# PSU_MGTAVTT_Buck.net
KiCad netlist of a schematic drawn in Altium Designer
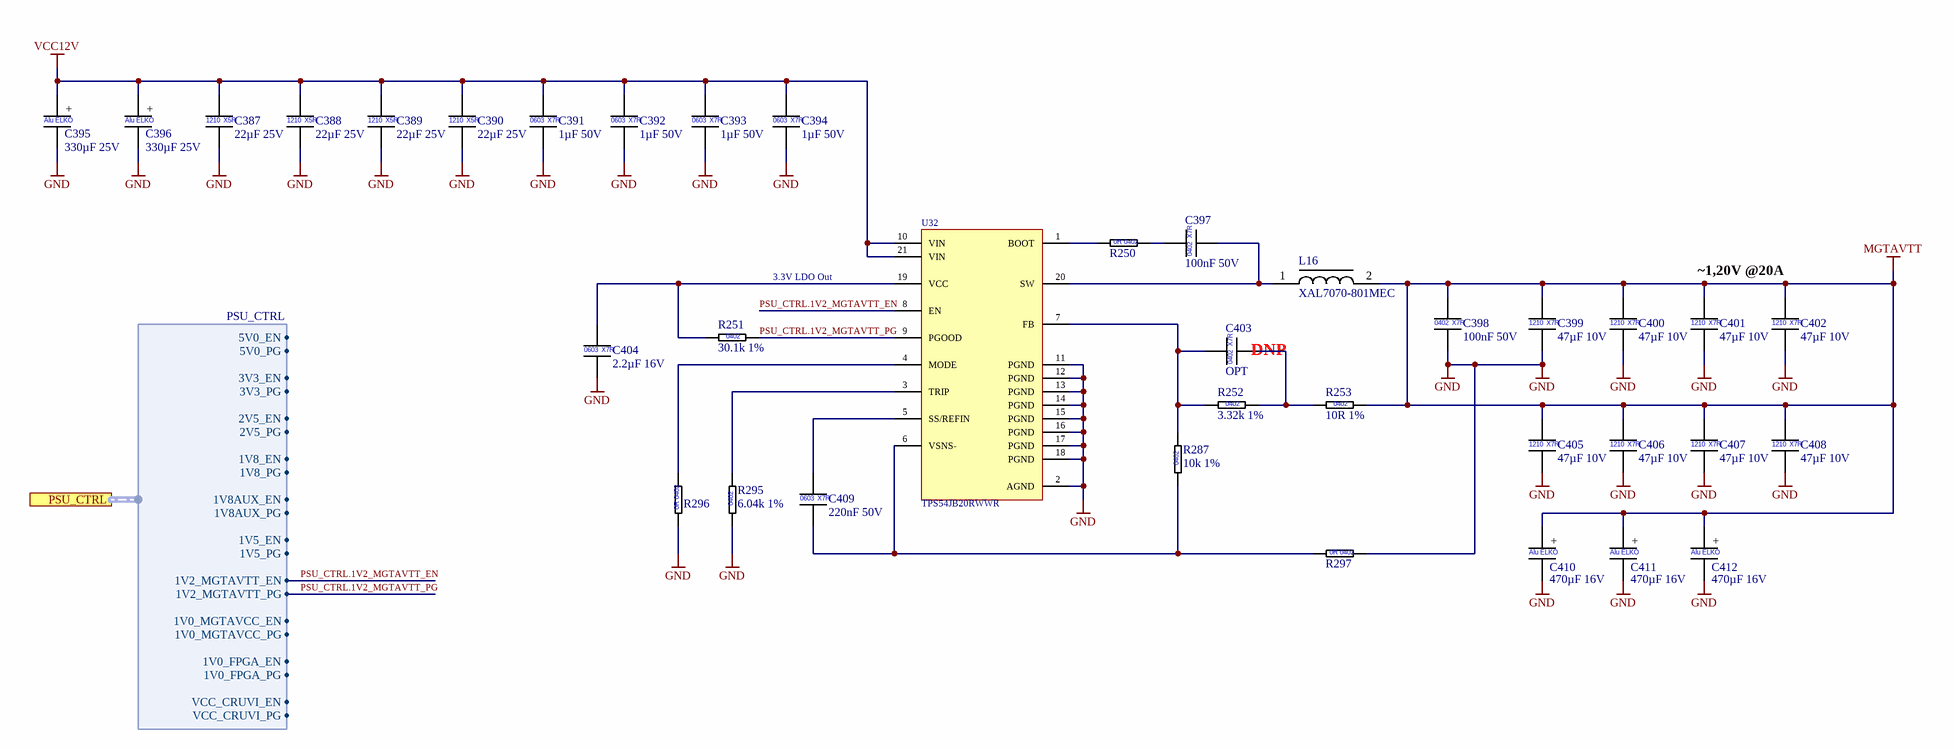
[diagram p0: PSU_MGTAVTT_Buck.SchDoc]

(export (version "E")
  (design (tool "Eeschema 10.0.6"))
  (components
    (comp (ref "C387")
      (value "22µF 25V")
      (footprint "Cap:CAP_1210")
      (description "Multilayer Ceramic Capacitors MLCC - SMD/SMT 1210 25VDC")
      (libsource (lib "Cap") (part "CAP_1210_22µF_25V"))
    )
    (comp (ref "C388")
      (value "22µF 25V")
      (footprint "Cap:CAP_1210")
      (description "Multilayer Ceramic Capacitors MLCC - SMD/SMT 1210 25VDC")
      (libsource (lib "Cap") (part "CAP_1210_22µF_25V"))
    )
    (comp (ref "C389")
      (value "22µF 25V")
      (footprint "Cap:CAP_1210")
      (description "Multilayer Ceramic Capacitors MLCC - SMD/SMT 1210 25VDC")
      (libsource (lib "Cap") (part "CAP_1210_22µF_25V"))
    )
    (comp (ref "C390")
      (value "22µF 25V")
      (footprint "Cap:CAP_1210")
      (description "Multilayer Ceramic Capacitors MLCC - SMD/SMT 1210 25VDC")
      (libsource (lib "Cap") (part "CAP_1210_22µF_25V"))
    )
    (comp (ref "C391")
      (value "1µF 50V")
      (footprint "CAP_0603")
      (description "Multilayer Ceramic Capacitors MLCC - SMD/SMT 50V 1uF X7R 0603 10%")
      (libsource (lib "Cap") (part "CAP_0603_1µF_50V_X7R_10%"))
    )
    (comp (ref "C392")
      (value "1µF 50V")
      (footprint "CAP_0603")
      (description "Multilayer Ceramic Capacitors MLCC - SMD/SMT 50V 1uF X7R 0603 10%")
      (libsource (lib "Cap") (part "CAP_0603_1µF_50V_X7R_10%"))
    )
    (comp (ref "C393")
      (value "1µF 50V")
      (footprint "CAP_0603")
      (description "Multilayer Ceramic Capacitors MLCC - SMD/SMT 50V 1uF X7R 0603 10%")
      (libsource (lib "Cap") (part "CAP_0603_1µF_50V_X7R_10%"))
    )
    (comp (ref "C394")
      (value "1µF 50V")
      (footprint "CAP_0603")
      (description "Multilayer Ceramic Capacitors MLCC - SMD/SMT 50V 1uF X7R 0603 10%")
      (libsource (lib "Cap") (part "CAP_0603_1µF_50V_X7R_10%"))
    )
    (comp (ref "C395")
      (value "330µF 25V")
      (footprint "Cap:WCAP-PTG5_D10H12.5")
      (description "Organische Polymer-Aluminiumkondensatoren 330uF 25 Volts 20% AEC-Q200")
      (libsource (lib "Cap") (part "CAP_D10L12.5_330µF_25V"))
    )
    (comp (ref "C396")
      (value "330µF 25V")
      (footprint "Cap:WCAP-PTG5_D10H12.5")
      (description "Organische Polymer-Aluminiumkondensatoren 330uF 25 Volts 20% AEC-Q200")
      (libsource (lib "Cap") (part "CAP_D10L12.5_330µF_25V"))
    )
    (comp (ref "C397")
      (value "100nF 50V")
      (footprint "Cap:CAP_0402")
      (description "Multilayer Ceramic Capacitors MLCC - SMD/SMT 0402 50VDC")
      (libsource (lib "Cap") (part "CAP_0402_100nF_50V"))
    )
    (comp (ref "C398")
      (value "100nF 50V")
      (footprint "Cap:CAP_0402")
      (description "Multilayer Ceramic Capacitors MLCC - SMD/SMT 0402 50VDC")
      (libsource (lib "") (part "CAP_0402_100nF_50V_1"))
    )
    (comp (ref "C399")
      (value "47µF 10V")
      (footprint "Cap:CAP_1210")
      (description "Multilayer Ceramic Capacitors MLCC - SMD/SMT 47 uF 10 VDC 10% 1210 X7R")
      (libsource (lib "Cap") (part "CAP_1210_47µF_10V_X7R_10%"))
    )
    (comp (ref "C400")
      (value "47µF 10V")
      (footprint "Cap:CAP_1210")
      (description "Multilayer Ceramic Capacitors MLCC - SMD/SMT 47 uF 10 VDC 10% 1210 X7R")
      (libsource (lib "Cap") (part "CAP_1210_47µF_10V_X7R_10%"))
    )
    (comp (ref "C401")
      (value "47µF 10V")
      (footprint "Cap:CAP_1210")
      (description "Multilayer Ceramic Capacitors MLCC - SMD/SMT 47 uF 10 VDC 10% 1210 X7R")
      (libsource (lib "Cap") (part "CAP_1210_47µF_10V_X7R_10%"))
    )
    (comp (ref "C402")
      (value "47µF 10V")
      (footprint "Cap:CAP_1210")
      (description "Multilayer Ceramic Capacitors MLCC - SMD/SMT 47 uF 10 VDC 10% 1210 X7R")
      (libsource (lib "Cap") (part "CAP_1210_47µF_10V_X7R_10%"))
    )
    (comp (ref "C403")
      (value "OPT")
      (footprint "Cap:CAP_0402")
      (description "Multilayer Ceramic Capacitors MLCC - SMD/SMT 0402 Optional Placeholder")
      (libsource (lib "Cap") (part "CAP_0402_OPT"))
    )
    (comp (ref "C404")
      (value "2.2µF 16V")
      (footprint "Cap:CAP_0603")
      (description "Multilayer Ceramic Capacitors MLCC - SMD/SMT 2.2 uF 16 VDC 10% 0603 X7R")
      (libsource (lib "Cap") (part "CAP_0603_2.2µF_16V_X7R_10%"))
    )
    (comp (ref "C405")
      (value "47µF 10V")
      (footprint "Cap:CAP_1210")
      (description "Multilayer Ceramic Capacitors MLCC - SMD/SMT 47 uF 10 VDC 10% 1210 X7R")
      (libsource (lib "Cap") (part "CAP_1210_47µF_10V_X7R_10%"))
    )
    (comp (ref "C406")
      (value "47µF 10V")
      (footprint "Cap:CAP_1210")
      (description "Multilayer Ceramic Capacitors MLCC - SMD/SMT 47 uF 10 VDC 10% 1210 X7R")
      (libsource (lib "Cap") (part "CAP_1210_47µF_10V_X7R_10%"))
    )
    (comp (ref "C407")
      (value "47µF 10V")
      (footprint "Cap:CAP_1210")
      (description "Multilayer Ceramic Capacitors MLCC - SMD/SMT 47 uF 10 VDC 10% 1210 X7R")
      (libsource (lib "Cap") (part "CAP_1210_47µF_10V_X7R_10%"))
    )
    (comp (ref "C408")
      (value "47µF 10V")
      (footprint "Cap:CAP_1210")
      (description "Multilayer Ceramic Capacitors MLCC - SMD/SMT 47 uF 10 VDC 10% 1210 X7R")
      (libsource (lib "Cap") (part "CAP_1210_47µF_10V_X7R_10%"))
    )
    (comp (ref "C409")
      (value "220nF 50V")
      (footprint "CAP_0603")
      (description "Multilayer Ceramic Capacitors MLCC - SMD/SMT 0.22 uF 50 VDC 10% 0603 X7R")
      (libsource (lib "Cap") (part "CAP_0603_220nF_50V_X7R_10%"))
    )
    (comp (ref "C410")
      (value "470µF 16V")
      (footprint "Cap:WCAP-PTG5_D8H13")
      (description "Organische Polymer-Aluminiumkondensatoren 470uF 16 Volts 20%")
      (libsource (lib "Cap") (part "CAP_D8L9_470µF_16V"))
    )
    (comp (ref "C411")
      (value "470µF 16V")
      (footprint "Cap:WCAP-PTG5_D8H13")
      (description "Organische Polymer-Aluminiumkondensatoren 470uF 16 Volts 20%")
      (libsource (lib "Cap") (part "CAP_D8L9_470µF_16V"))
    )
    (comp (ref "C412")
      (value "470µF 16V")
      (footprint "Cap:WCAP-PTG5_D8H13")
      (description "Organische Polymer-Aluminiumkondensatoren 470uF 16 Volts 20%")
      (libsource (lib "Cap") (part "CAP_D8L9_470µF_16V"))
    )
    (comp (ref "L16")
      (value "XAL7070-801MEC")
      (footprint "indc:COILCRAFT_XAL7070")
      (description "Power Inductors - SMD 800nH Shld 20% 25.8A 2.29mOhms AECQ200")
      (libsource (lib "Indc") (part "XAL7070-801MEC_Power Inductors SMD 800nH Shld 20% 25.8A 2.29mOhms AECQ200"))
    )
    (comp (ref "R250")
      (value "0R Jumper")
      (footprint "res:RES_0402")
      (description "Thick Film Resistors - SMD 0Ohm")
      (libsource (lib "Res") (part "RES_0402_0R Jumper"))
    )
    (comp (ref "R251")
      (value "30.1k 1%")
      (footprint "res:RES_0402")
      (description "Thick Film Resistors - SMD 30.1kOhm 1%")
      (libsource (lib "Res") (part "RES_0402_30.1k_1%"))
    )
    (comp (ref "R252")
      (value "3.32k 1%")
      (footprint "res:RES_0402")
      (description "Thick Film Resistors - SMD 3.32kOhm 1%")
      (libsource (lib "Res") (part "RES_0402_3.32k_1%"))
    )
    (comp (ref "R253")
      (value "10R 1%")
      (footprint "res:RES_0402")
      (description "Thick Film Resistors - SMD 10Ohm 1%")
      (libsource (lib "Res") (part "RES_0402_10R_1%"))
    )
    (comp (ref "R287")
      (value "10k 1%")
      (footprint "Res:RES_0402")
      (description "Thick Film Resistors - SMD 10kOhm 1%")
      (libsource (lib "Res") (part "RES_0402_10k_1%"))
    )
    (comp (ref "R295")
      (value "6.04k 1%")
      (footprint "Res:RES_0402")
      (description "Thick Film Resistors - SMD 6.04kOhm 1%")
      (libsource (lib "Res") (part "RES_0402_6.04k_1%"))
    )
    (comp (ref "R296")
      (value "0R Jumper")
      (footprint "res:RES_0402")
      (description "Thick Film Resistors - SMD 0Ohm")
      (libsource (lib "Res") (part "RES_0402_0R Jumper"))
    )
    (comp (ref "R297")
      (value "0R Jumper")
      (footprint "res:RES_0402")
      (description "Thick Film Resistors - SMD 0Ohm")
      (libsource (lib "Res") (part "RES_0402_0R Jumper"))
    )
    (comp (ref "U32")
      (value "TPS54JB20RWWR")
      (footprint "power:VQFN-HR21_RWW0021A")
      (description "Switching Voltage Regulators 2.7-V to 16-V input 20-A synchronous Buck")
      (libsource (lib "Power") (part "TPS54JB20RWWR_Switching Voltage Regulators 2.7-V to 16-V input 20-A synchronous Buck"))
    )
  )
  (nets
    (net (code "2") (name "/PSU_CTRL.1V2_MGTAVTT_EN") (class "Default")
      (node (ref "U32") (pin "8") (pinfunction "EN_8") (pintype "passive"))
    )
    (net (code "3") (name "/PSU_CTRL.1V2_MGTAVTT_PG") (class "Default")
      (node (ref "R251") (pin "2") (pinfunction "2_2") (pintype "passive"))
      (node (ref "U32") (pin "9") (pinfunction "PGOOD_9") (pintype "passive"))
    )
    (net (code "5") (name "GND") (class "Default")
      (node (ref "C387") (pin "2") (pinfunction "2_2") (pintype "passive"))
      (node (ref "C388") (pin "2") (pinfunction "2_2") (pintype "passive"))
      (node (ref "C389") (pin "2") (pinfunction "2_2") (pintype "passive"))
      (node (ref "C390") (pin "2") (pinfunction "2_2") (pintype "passive"))
      (node (ref "C391") (pin "2") (pinfunction "2_2") (pintype "passive"))
      (node (ref "C392") (pin "2") (pinfunction "2_2") (pintype "passive"))
      (node (ref "C393") (pin "2") (pinfunction "2_2") (pintype "passive"))
      (node (ref "C394") (pin "2") (pinfunction "2_2") (pintype "passive"))
      (node (ref "C395") (pin "2") (pinfunction "2_2") (pintype "passive"))
      (node (ref "C396") (pin "2") (pinfunction "2_2") (pintype "passive"))
      (node (ref "C398") (pin "2") (pinfunction "2_2") (pintype "passive"))
      (node (ref "C399") (pin "2") (pinfunction "2_2") (pintype "passive"))
      (node (ref "C400") (pin "2") (pinfunction "2_2") (pintype "passive"))
      (node (ref "C401") (pin "2") (pinfunction "2_2") (pintype "passive"))
      (node (ref "C402") (pin "2") (pinfunction "2_2") (pintype "passive"))
      (node (ref "C404") (pin "2") (pinfunction "2_2") (pintype "passive"))
      (node (ref "C405") (pin "2") (pinfunction "2_2") (pintype "passive"))
      (node (ref "C406") (pin "2") (pinfunction "2_2") (pintype "passive"))
      (node (ref "C407") (pin "2") (pinfunction "2_2") (pintype "passive"))
      (node (ref "C408") (pin "2") (pinfunction "2_2") (pintype "passive"))
      (node (ref "C410") (pin "2") (pinfunction "2_2") (pintype "passive"))
      (node (ref "C411") (pin "2") (pinfunction "2_2") (pintype "passive"))
      (node (ref "C412") (pin "2") (pinfunction "2_2") (pintype "passive"))
      (node (ref "R295") (pin "1") (pinfunction "1_1") (pintype "passive"))
      (node (ref "R296") (pin "1") (pinfunction "1_1") (pintype "passive"))
      (node (ref "R297") (pin "2") (pinfunction "2_2") (pintype "passive"))
      (node (ref "U32") (pin "11") (pinfunction "PGND_11") (pintype "passive"))
      (node (ref "U32") (pin "12") (pinfunction "PGND_12") (pintype "passive"))
      (node (ref "U32") (pin "13") (pinfunction "PGND_13") (pintype "passive"))
      (node (ref "U32") (pin "14") (pinfunction "PGND_14") (pintype "passive"))
      (node (ref "U32") (pin "15") (pinfunction "PGND_15") (pintype "passive"))
      (node (ref "U32") (pin "16") (pinfunction "PGND_16") (pintype "passive"))
      (node (ref "U32") (pin "17") (pinfunction "PGND_17") (pintype "passive"))
      (node (ref "U32") (pin "18") (pinfunction "PGND_18") (pintype "passive"))
      (node (ref "U32") (pin "2") (pinfunction "AGND_2") (pintype "passive"))
    )
    (net (code "6") (name "MGTAVTT") (class "Default")
      (node (ref "C398") (pin "1") (pinfunction "1_1") (pintype "passive"))
      (node (ref "C399") (pin "1") (pinfunction "1_1") (pintype "passive"))
      (node (ref "C400") (pin "1") (pinfunction "1_1") (pintype "passive"))
      (node (ref "C401") (pin "1") (pinfunction "1_1") (pintype "passive"))
      (node (ref "C402") (pin "1") (pinfunction "1_1") (pintype "passive"))
      (node (ref "C405") (pin "1") (pinfunction "1_1") (pintype "passive"))
      (node (ref "C406") (pin "1") (pinfunction "1_1") (pintype "passive"))
      (node (ref "C407") (pin "1") (pinfunction "1_1") (pintype "passive"))
      (node (ref "C408") (pin "1") (pinfunction "1_1") (pintype "passive"))
      (node (ref "C410") (pin "1") (pinfunction "1_1") (pintype "passive"))
      (node (ref "C411") (pin "1") (pinfunction "1_1") (pintype "passive"))
      (node (ref "C412") (pin "1") (pinfunction "1_1") (pintype "passive"))
      (node (ref "L16") (pin "2") (pinfunction "2_2") (pintype "passive"))
      (node (ref "R253") (pin "2") (pinfunction "2_2") (pintype "passive"))
    )
    (net (code "7") (name "Net-(C397-Pad1)") (class "Default")
      (node (ref "C397") (pin "1") (pinfunction "1_1") (pintype "passive"))
      (node (ref "R250") (pin "2") (pinfunction "2_2") (pintype "passive"))
    )
    (net (code "8") (name "Net-(C403-Pad2)") (class "Default")
      (node (ref "C403") (pin "2") (pinfunction "2_2") (pintype "passive"))
      (node (ref "R252") (pin "2") (pinfunction "2_2") (pintype "passive"))
      (node (ref "R253") (pin "1") (pinfunction "1_1") (pintype "passive"))
    )
    (net (code "9") (name "Net-(U32-BOOT)") (class "Default")
      (node (ref "R250") (pin "1") (pinfunction "1_1") (pintype "passive"))
      (node (ref "U32") (pin "1") (pinfunction "BOOT_1") (pintype "passive"))
    )
    (net (code "10") (name "Net-(U32-FB)") (class "Default")
      (node (ref "C403") (pin "1") (pinfunction "1_1") (pintype "passive"))
      (node (ref "R252") (pin "1") (pinfunction "1_1") (pintype "passive"))
      (node (ref "R287") (pin "2") (pinfunction "2_2") (pintype "passive"))
      (node (ref "U32") (pin "7") (pinfunction "FB_7") (pintype "passive"))
    )
    (net (code "11") (name "Net-(U32-MODE)") (class "Default")
      (node (ref "R296") (pin "2") (pinfunction "2_2") (pintype "passive"))
      (node (ref "U32") (pin "4") (pinfunction "MODE_4") (pintype "passive"))
    )
    (net (code "12") (name "Net-(U32-SS{slash}REFIN)") (class "Default")
      (node (ref "C409") (pin "1") (pinfunction "1_1") (pintype "passive"))
      (node (ref "U32") (pin "5") (pinfunction "SS/REFIN_5") (pintype "passive"))
    )
    (net (code "13") (name "Net-(U32-SW)") (class "Default")
      (node (ref "C397") (pin "2") (pinfunction "2_2") (pintype "passive"))
      (node (ref "L16") (pin "1") (pinfunction "1_1") (pintype "passive"))
      (node (ref "U32") (pin "20") (pinfunction "SW_20") (pintype "passive"))
    )
    (net (code "14") (name "Net-(U32-TRIP)") (class "Default")
      (node (ref "R295") (pin "2") (pinfunction "2_2") (pintype "passive"))
      (node (ref "U32") (pin "3") (pinfunction "TRIP_3") (pintype "passive"))
    )
    (net (code "15") (name "Net-(U32-VCC)") (class "Default")
      (node (ref "C404") (pin "1") (pinfunction "1_1") (pintype "passive"))
      (node (ref "R251") (pin "1") (pinfunction "1_1") (pintype "passive"))
      (node (ref "U32") (pin "19") (pinfunction "VCC_19") (pintype "passive"))
    )
    (net (code "16") (name "Net-(U32-VSNS-)") (class "Default")
      (node (ref "C409") (pin "2") (pinfunction "2_2") (pintype "passive"))
      (node (ref "R287") (pin "1") (pinfunction "1_1") (pintype "passive"))
      (node (ref "R297") (pin "1") (pinfunction "1_1") (pintype "passive"))
      (node (ref "U32") (pin "6") (pinfunction "VSNS-_6") (pintype "passive"))
    )
    (net (code "17") (name "VCC12V") (class "Default")
      (node (ref "C387") (pin "1") (pinfunction "1_1") (pintype "passive"))
      (node (ref "C388") (pin "1") (pinfunction "1_1") (pintype "passive"))
      (node (ref "C389") (pin "1") (pinfunction "1_1") (pintype "passive"))
      (node (ref "C390") (pin "1") (pinfunction "1_1") (pintype "passive"))
      (node (ref "C391") (pin "1") (pinfunction "1_1") (pintype "passive"))
      (node (ref "C392") (pin "1") (pinfunction "1_1") (pintype "passive"))
      (node (ref "C393") (pin "1") (pinfunction "1_1") (pintype "passive"))
      (node (ref "C394") (pin "1") (pinfunction "1_1") (pintype "passive"))
      (node (ref "C395") (pin "1") (pinfunction "1_1") (pintype "passive"))
      (node (ref "C396") (pin "1") (pinfunction "1_1") (pintype "passive"))
      (node (ref "U32") (pin "10") (pinfunction "VIN_10") (pintype "passive"))
      (node (ref "U32") (pin "21") (pinfunction "VIN_21") (pintype "passive"))
    )
  )
)
